# Schematic.net
KiCad netlist of a schematic drawn in EasyEDA
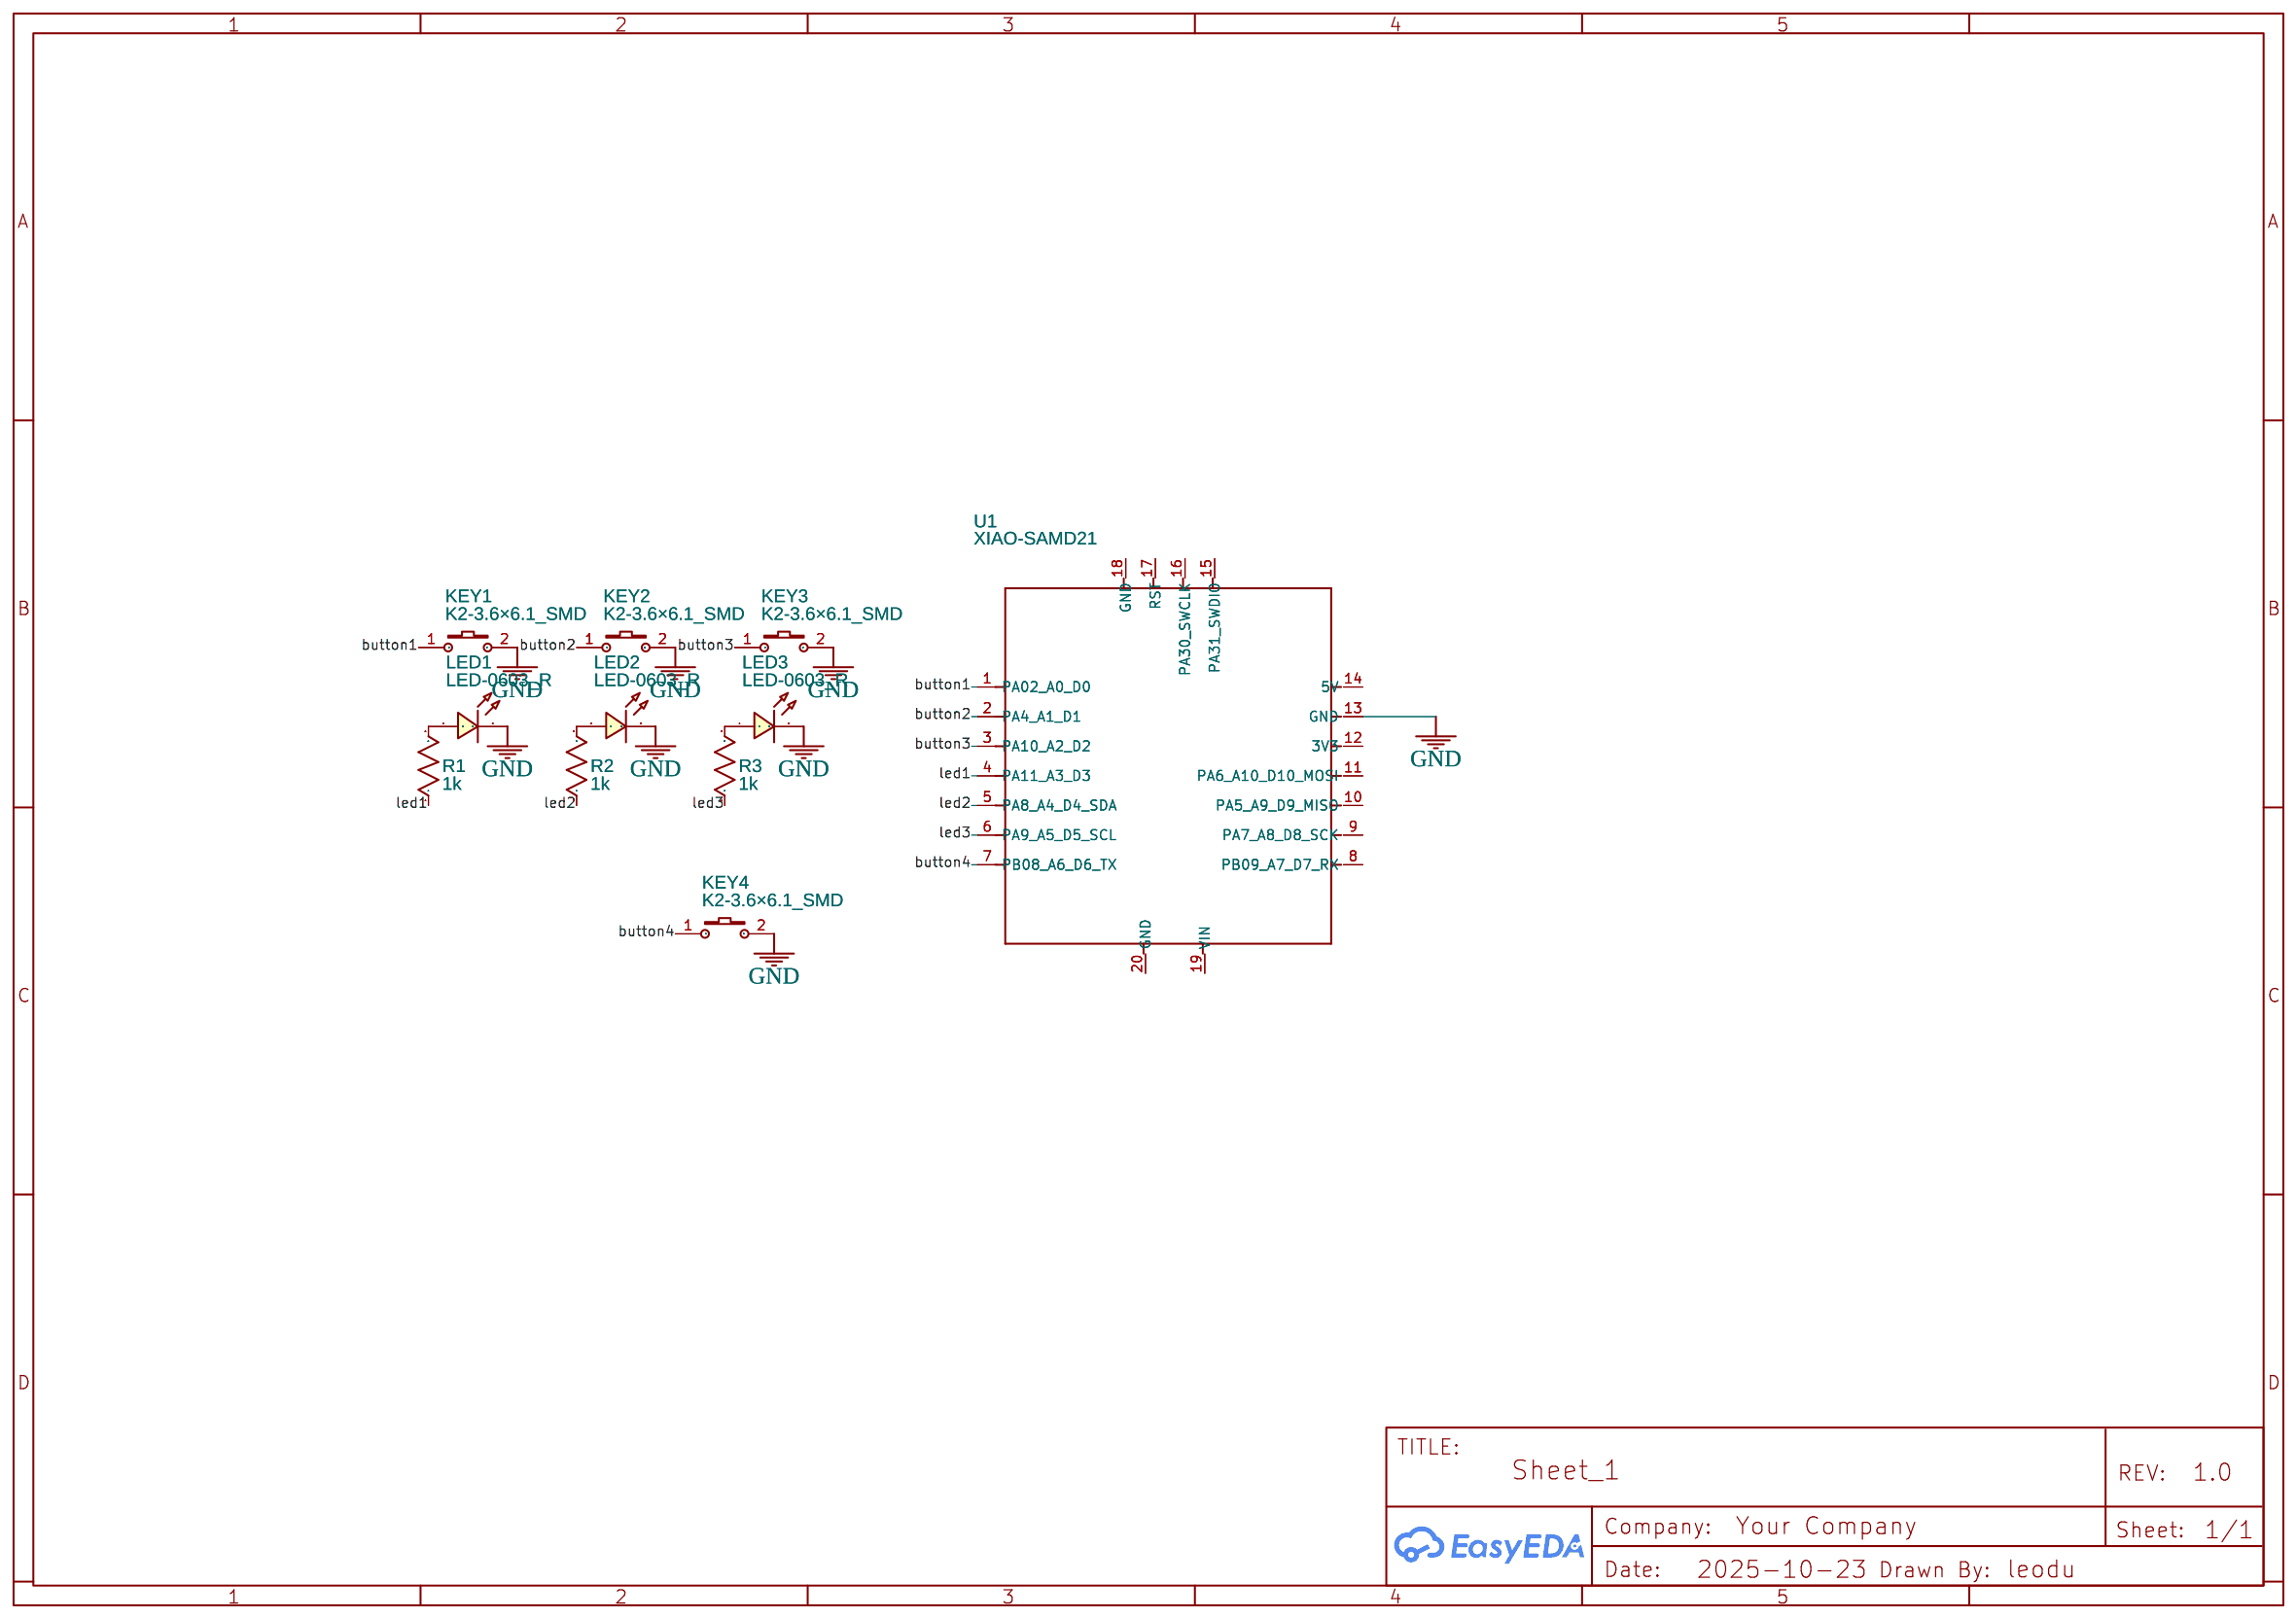
[diagram p0: schematic sheet]

(export (version "E")
  (design (tool "Eeschema 10.0.6"))
  (components
    (comp (ref "KEY1")
      (value "K2-3.6×6.1_SMD")
      (fields (field (name "Manufacturer Part") "K2-1107ST-A4SW-06"))
      (libsource (lib "") (part "K2-3.6×6.1_SMD"))
    )
    (comp (ref "KEY2")
      (value "K2-3.6×6.1_SMD")
      (fields (field (name "Manufacturer Part") "K2-1107ST-A4SW-06"))
      (libsource (lib "") (part "K2-3.6×6.1_SMD"))
    )
    (comp (ref "KEY3")
      (value "K2-3.6×6.1_SMD")
      (fields (field (name "Manufacturer Part") "K2-1107ST-A4SW-06"))
      (libsource (lib "") (part "K2-3.6×6.1_SMD"))
    )
    (comp (ref "KEY4")
      (value "K2-3.6×6.1_SMD")
      (fields (field (name "Manufacturer Part") "K2-1107ST-A4SW-06"))
      (libsource (lib "") (part "K2-3.6×6.1_SMD"))
    )
    (comp (ref "LED1")
      (value "LED-0603_R")
      (fields
        (field (name "Manufacturer Part") "19-217/R6C-AL1M2VY/3T")
        (field (name "Manufacturer") "EVERLIGHT(台湾亿光)")
      )
      (libsource (lib "") (part "LED-0603_R"))
    )
    (comp (ref "LED2")
      (value "LED-0603_R")
      (fields
        (field (name "Manufacturer Part") "19-217/R6C-AL1M2VY/3T")
        (field (name "Manufacturer") "EVERLIGHT(台湾亿光)")
      )
      (libsource (lib "") (part "LED-0603_R"))
    )
    (comp (ref "LED3")
      (value "LED-0603_R")
      (fields
        (field (name "Manufacturer Part") "19-217/R6C-AL1M2VY/3T")
        (field (name "Manufacturer") "EVERLIGHT(台湾亿光)")
      )
      (libsource (lib "") (part "LED-0603_R"))
    )
    (comp (ref "R1") (value "1k") (libsource (lib "") (part "R_0603_US")))
    (comp (ref "R2") (value "1k") (libsource (lib "") (part "R_0603_US")))
    (comp (ref "R3") (value "1k") (libsource (lib "") (part "R_0603_US")))
    (comp (ref "U1") (value "XIAO-SAMD21") (libsource (lib "") (part "XIAO-SAMD21")))
  )
  (nets
    (net (code "1") (name "/button1") (class "Default")
      (node (ref "KEY1") (pin "1") (pinfunction "1_1") (pintype "unspecified"))
      (node (ref "U1") (pin "1") (pinfunction "PA02_A0_D0_1") (pintype "bidirectional"))
    )
    (net (code "2") (name "/button2") (class "Default")
      (node (ref "KEY2") (pin "1") (pinfunction "1_1") (pintype "unspecified"))
      (node (ref "U1") (pin "2") (pinfunction "PA4_A1_D1_2") (pintype "bidirectional"))
    )
    (net (code "3") (name "/button3") (class "Default")
      (node (ref "KEY3") (pin "1") (pinfunction "1_1") (pintype "unspecified"))
      (node (ref "U1") (pin "3") (pinfunction "PA10_A2_D2_3") (pintype "bidirectional"))
    )
    (net (code "4") (name "/button4") (class "Default")
      (node (ref "KEY4") (pin "1") (pinfunction "1_1") (pintype "unspecified"))
      (node (ref "U1") (pin "7") (pinfunction "PB08_A6_D6_TX_7") (pintype "bidirectional"))
    )
    (net (code "5") (name "/led1") (class "Default")
      (node (ref "R1") (pin "1") (pinfunction "1_1") (pintype "unspecified"))
      (node (ref "U1") (pin "4") (pinfunction "PA11_A3_D3_4") (pintype "bidirectional"))
    )
    (net (code "6") (name "/led2") (class "Default")
      (node (ref "R2") (pin "1") (pinfunction "1_1") (pintype "unspecified"))
      (node (ref "U1") (pin "5") (pinfunction "PA8_A4_D4_SDA_5") (pintype "bidirectional"))
    )
    (net (code "7") (name "/led3") (class "Default")
      (node (ref "R3") (pin "1") (pinfunction "1_1") (pintype "unspecified"))
      (node (ref "U1") (pin "6") (pinfunction "PA9_A5_D5_SCL_6") (pintype "bidirectional"))
    )
    (net (code "8") (name "GND") (class "Default")
      (node (ref "KEY1") (pin "2") (pinfunction "2_2") (pintype "unspecified"))
      (node (ref "KEY2") (pin "2") (pinfunction "2_2") (pintype "unspecified"))
      (node (ref "KEY3") (pin "2") (pinfunction "2_2") (pintype "unspecified"))
      (node (ref "KEY4") (pin "2") (pinfunction "2_2") (pintype "unspecified"))
      (node (ref "LED1") (pin "2") (pinfunction "2_2") (pintype "unspecified"))
      (node (ref "LED2") (pin "2") (pinfunction "2_2") (pintype "unspecified"))
      (node (ref "LED3") (pin "2") (pinfunction "2_2") (pintype "unspecified"))
      (node (ref "U1") (pin "13") (pinfunction "GND_13") (pintype "bidirectional"))
    )
    (net (code "9") (name "Net-(LED1-Pad1)") (class "Default")
      (node (ref "LED1") (pin "1") (pinfunction "1_1") (pintype "unspecified"))
      (node (ref "R1") (pin "2") (pinfunction "2_2") (pintype "unspecified"))
    )
    (net (code "10") (name "Net-(LED2-Pad1)") (class "Default")
      (node (ref "LED2") (pin "1") (pinfunction "1_1") (pintype "unspecified"))
      (node (ref "R2") (pin "2") (pinfunction "2_2") (pintype "unspecified"))
    )
    (net (code "11") (name "Net-(LED3-Pad1)") (class "Default")
      (node (ref "LED3") (pin "1") (pinfunction "1_1") (pintype "unspecified"))
      (node (ref "R3") (pin "2") (pinfunction "2_2") (pintype "unspecified"))
    )
    (net (code "12") (name "unconnected-(U1-3V3-Pad12)") (class "Default")
      (node (ref "U1") (pin "12") (pinfunction "3V3_12") (pintype "bidirectional"))
    )
    (net (code "13") (name "unconnected-(U1-5V-Pad14)") (class "Default")
      (node (ref "U1") (pin "14") (pinfunction "5V_14") (pintype "bidirectional"))
    )
    (net (code "14") (name "unconnected-(U1-GND-Pad18)") (class "Default")
      (node (ref "U1") (pin "18") (pinfunction "GND_18") (pintype "bidirectional"))
    )
    (net (code "15") (name "unconnected-(U1-GND-Pad20)") (class "Default")
      (node (ref "U1") (pin "20") (pinfunction "GND_20") (pintype "bidirectional"))
    )
    (net (code "16") (name "unconnected-(U1-PA5_A9_D9_MISO-Pad10)") (class "Default")
      (node (ref "U1") (pin "10") (pinfunction "PA5_A9_D9_MISO_10") (pintype "bidirectional"))
    )
    (net (code "17") (name "unconnected-(U1-PA6_A10_D10_MOSI-Pad11)") (class "Default")
      (node (ref "U1") (pin "11") (pinfunction "PA6_A10_D10_MOSI_11") (pintype "bidirectional"))
    )
    (net (code "18") (name "unconnected-(U1-PA7_A8_D8_SCK-Pad9)") (class "Default")
      (node (ref "U1") (pin "9") (pinfunction "PA7_A8_D8_SCK_9") (pintype "bidirectional"))
    )
    (net (code "19") (name "unconnected-(U1-PA30_SWCLK-Pad16)") (class "Default")
      (node (ref "U1") (pin "16") (pinfunction "PA30_SWCLK_16") (pintype "bidirectional"))
    )
    (net (code "20") (name "unconnected-(U1-PA31_SWDIO-Pad15)") (class "Default")
      (node (ref "U1") (pin "15") (pinfunction "PA31_SWDIO_15") (pintype "bidirectional"))
    )
    (net (code "21") (name "unconnected-(U1-PB09_A7_D7_RX-Pad8)") (class "Default")
      (node (ref "U1") (pin "8") (pinfunction "PB09_A7_D7_RX_8") (pintype "bidirectional"))
    )
    (net (code "22") (name "unconnected-(U1-RST-Pad17)") (class "Default")
      (node (ref "U1") (pin "17") (pinfunction "RST_17") (pintype "bidirectional"))
    )
    (net (code "23") (name "unconnected-(U1-VIN-Pad19)") (class "Default")
      (node (ref "U1") (pin "19") (pinfunction "VIN_19") (pintype "bidirectional"))
    )
  )
)
